# 6_H-bridge2.net
KiCad netlist of a schematic drawn in Altium Designer
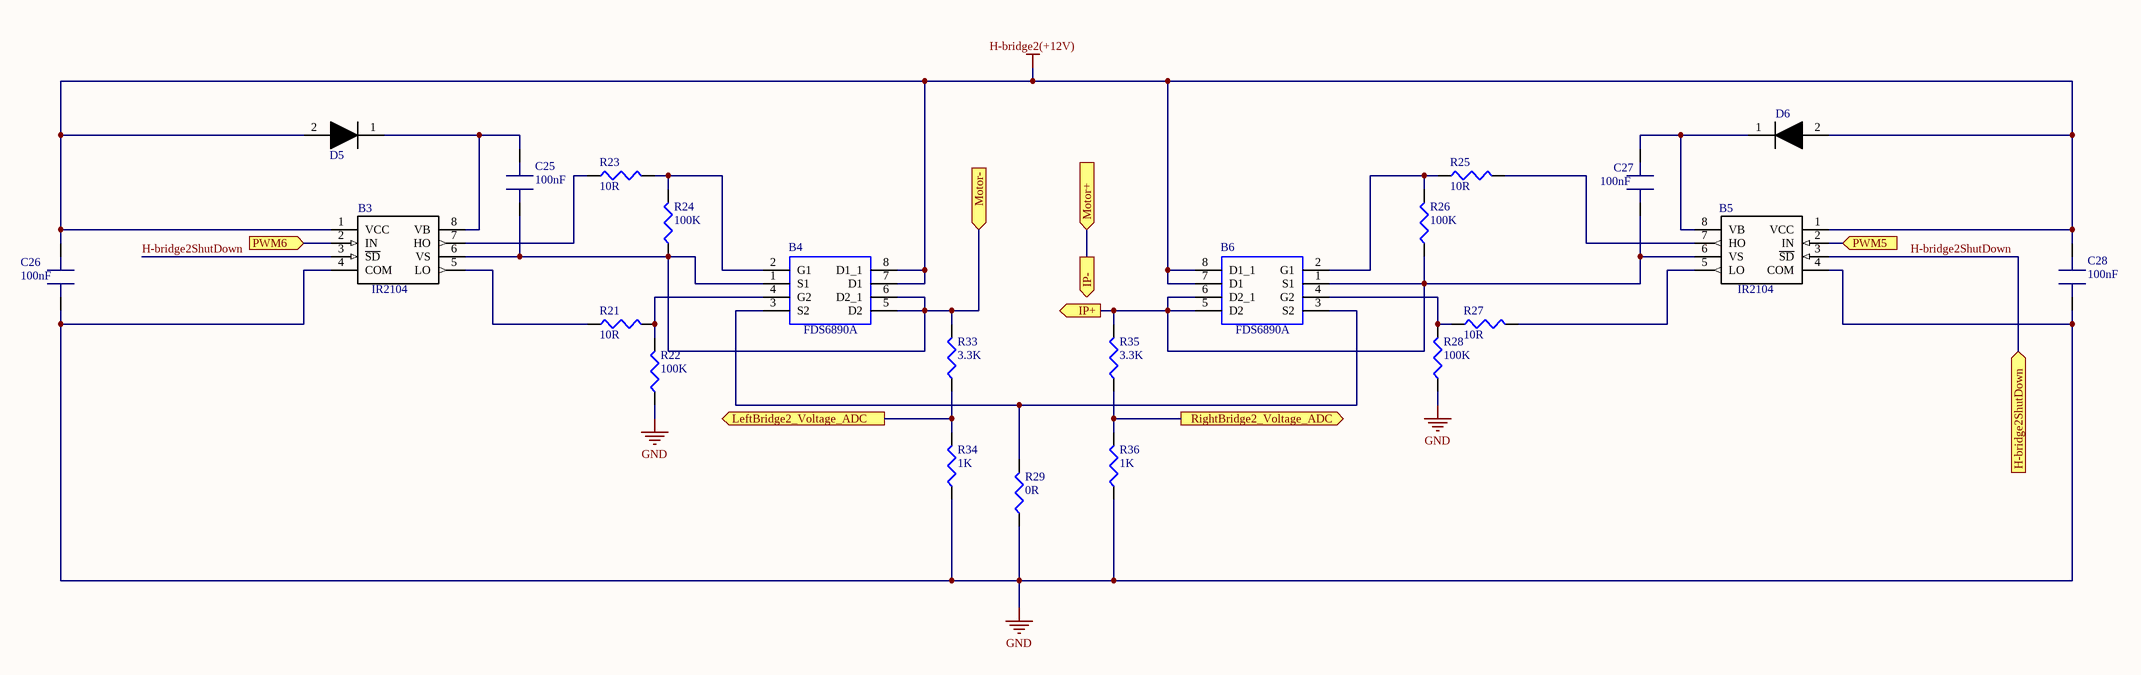
[diagram p0: [6]H-bridge2.SchDoc]

(export (version "E")
  (design (tool "Eeschema 10.0.6"))
  (components
    (comp (ref "B3")
      (value "IR2104")
      (footprint "*SOIC127P600X175-8N")
      (fields
        (field (name "MP") "IR2104STRPBF")
        (field (name "DIGI-KEY_PART_NUMBER") "IR2104SPBFCT-ND")
        (field (name "MF") "Infineon Technologies")
      )
      (libsource (lib "IR2104STRPBF") (part "IR2104STRPBF"))
    )
    (comp (ref "B4")
      (value "FDS6890A")
      (footprint "SOIC127P600X175-8N")
      (description "FDS6890A, Dual N-channel MOSFET Transistor 7.5 A 20 V, 8-Pin SOIC")
      (fields (field (name "RS PART NUMBER") "6710633P") (field (name "MOUSER PART NUMBER") "512-FDS6890A"))
      (libsource (lib "FDS6890A") (part "FDS6890A"))
    )
    (comp (ref "B5")
      (value "IR2104")
      (footprint "*SOIC127P600X175-8N")
      (fields
        (field (name "MP") "IR2104STRPBF")
        (field (name "DIGI-KEY_PART_NUMBER") "IR2104SPBFCT-ND")
        (field (name "MF") "Infineon Technologies")
      )
      (libsource (lib "IR2104STRPBF") (part "IR2104STRPBF"))
    )
    (comp (ref "B6")
      (value "FDS6890A")
      (footprint "SOIC127P600X175-8N")
      (description "FDS6890A, Dual N-channel MOSFET Transistor 7.5 A 20 V, 8-Pin SOIC")
      (fields (field (name "RS PART NUMBER") "6710633P") (field (name "MOUSER PART NUMBER") "512-FDS6890A"))
      (libsource (lib "FDS6890A") (part "FDS6890A"))
    )
    (comp (ref "C25") (value "100nF") (footprint "cap_805") (libsource (lib "Driver") (part "cap805")))
    (comp (ref "C26") (value "100nF") (footprint "cap_805") (libsource (lib "Driver") (part "cap805")))
    (comp (ref "C27") (value "100nF") (footprint "cap_805") (libsource (lib "Driver") (part "cap805")))
    (comp (ref "C28") (value "100nF") (footprint "cap_805") (libsource (lib "Driver") (part "cap805")))
    (comp (ref "D5") (value "Doide_SS34") (footprint "Doide_SS34") (libsource (lib "CM") (part "Doide_SS34")))
    (comp (ref "D6") (value "Doide_SS34") (footprint "Doide_SS34") (libsource (lib "CM") (part "Doide_SS34")))
    (comp (ref "R21") (value "10R") (footprint "Res805") (libsource (lib "Driver") (part "Res805")))
    (comp (ref "R22") (value "100K") (footprint "Res805") (libsource (lib "Driver") (part "Res805")))
    (comp (ref "R23") (value "10R") (footprint "Res805") (libsource (lib "Driver") (part "Res805")))
    (comp (ref "R24") (value "100K") (footprint "Res805") (libsource (lib "Driver") (part "Res805")))
    (comp (ref "R25") (value "10R") (footprint "Res805") (libsource (lib "Driver") (part "Res805")))
    (comp (ref "R26") (value "100K") (footprint "Res805") (libsource (lib "Driver") (part "Res805")))
    (comp (ref "R27") (value "10R") (footprint "Res805") (libsource (lib "Driver") (part "Res805")))
    (comp (ref "R28") (value "100K") (footprint "Res805") (libsource (lib "Driver") (part "Res805")))
    (comp (ref "R29") (value "0R") (footprint "Res805") (libsource (lib "Driver") (part "Res805")))
    (comp (ref "R33") (value "3.3K") (footprint "Res805") (libsource (lib "Driver") (part "Res805")))
    (comp (ref "R34") (value "1K") (footprint "Res805") (libsource (lib "Driver") (part "Res805")))
    (comp (ref "R35") (value "3.3K") (footprint "Res805") (libsource (lib "Driver") (part "Res805")))
    (comp (ref "R36") (value "1K") (footprint "Res805") (libsource (lib "Driver") (part "Res805")))
  )
  (nets
    (net (code "1") (name "/H-bridge2ShutDown") (class "Default")
      (node (ref "B3") (pin "3") (pinfunction "~{SD}_3") (pintype "input"))
      (node (ref "B5") (pin "3") (pinfunction "~{SD}_3") (pintype "input"))
    )
    (net (code "2") (name "/IP+") (class "Default")
      (node (ref "B5") (pin "6") (pinfunction "VS_6") (pintype "power_in"))
      (node (ref "B6") (pin "1") (pinfunction "S1_1") (pintype "passive"))
      (node (ref "B6") (pin "5") (pinfunction "D2_5") (pintype "passive"))
      (node (ref "B6") (pin "6") (pinfunction "D2_1_6") (pintype "passive"))
      (node (ref "C27") (pin "1") (pinfunction "1_1") (pintype "passive"))
      (node (ref "R26") (pin "1") (pinfunction "1_1") (pintype "passive"))
      (node (ref "R35") (pin "2") (pinfunction "2_2") (pintype "passive"))
    )
    (net (code "4") (name "/LeftBridge2_Voltage_ADC") (class "Default")
      (node (ref "R33") (pin "1") (pinfunction "1_1") (pintype "passive"))
      (node (ref "R34") (pin "2") (pinfunction "2_2") (pintype "passive"))
    )
    (net (code "5") (name "/Motor-") (class "Default")
      (node (ref "B3") (pin "6") (pinfunction "VS_6") (pintype "power_in"))
      (node (ref "B4") (pin "1") (pinfunction "S1_1") (pintype "passive"))
      (node (ref "B4") (pin "5") (pinfunction "D2_5") (pintype "passive"))
      (node (ref "B4") (pin "6") (pinfunction "D2_1_6") (pintype "passive"))
      (node (ref "C25") (pin "1") (pinfunction "1_1") (pintype "passive"))
      (node (ref "R24") (pin "1") (pinfunction "1_1") (pintype "passive"))
      (node (ref "R33") (pin "2") (pinfunction "2_2") (pintype "passive"))
    )
    (net (code "6") (name "/PWM5") (class "Default")
      (node (ref "B5") (pin "2") (pinfunction "IN_2") (pintype "input"))
    )
    (net (code "7") (name "/PWM6") (class "Default")
      (node (ref "B3") (pin "2") (pinfunction "IN_2") (pintype "input"))
    )
    (net (code "8") (name "/RightBridge2_Voltage_ADC") (class "Default")
      (node (ref "R35") (pin "1") (pinfunction "1_1") (pintype "passive"))
      (node (ref "R36") (pin "2") (pinfunction "2_2") (pintype "passive"))
    )
    (net (code "9") (name "GND") (class "Default")
      (node (ref "B3") (pin "4") (pinfunction "COM_4") (pintype "passive"))
      (node (ref "B5") (pin "4") (pinfunction "COM_4") (pintype "passive"))
      (node (ref "C26") (pin "1") (pinfunction "1_1") (pintype "passive"))
      (node (ref "C28") (pin "1") (pinfunction "1_1") (pintype "passive"))
      (node (ref "R22") (pin "1") (pinfunction "1_1") (pintype "passive"))
      (node (ref "R28") (pin "1") (pinfunction "1_1") (pintype "passive"))
      (node (ref "R29") (pin "1") (pinfunction "1_1") (pintype "passive"))
      (node (ref "R34") (pin "1") (pinfunction "1_1") (pintype "passive"))
      (node (ref "R36") (pin "1") (pinfunction "1_1") (pintype "passive"))
    )
    (net (code "10") (name "H-bridge2(+12V)") (class "Default")
      (node (ref "B3") (pin "1") (pinfunction "VCC_1") (pintype "power_in"))
      (node (ref "B4") (pin "7") (pinfunction "D1_7") (pintype "passive"))
      (node (ref "B4") (pin "8") (pinfunction "D1_1_8") (pintype "passive"))
      (node (ref "B5") (pin "1") (pinfunction "VCC_1") (pintype "power_in"))
      (node (ref "B6") (pin "7") (pinfunction "D1_7") (pintype "passive"))
      (node (ref "B6") (pin "8") (pinfunction "D1_1_8") (pintype "passive"))
      (node (ref "C26") (pin "2") (pinfunction "2_2") (pintype "passive"))
      (node (ref "C28") (pin "2") (pinfunction "2_2") (pintype "passive"))
      (node (ref "D5") (pin "2") (pinfunction "2_2") (pintype "passive"))
      (node (ref "D6") (pin "2") (pinfunction "2_2") (pintype "passive"))
    )
    (net (code "11") (name "Net-(B3-HO)") (class "Default")
      (node (ref "B3") (pin "7") (pinfunction "HO_7") (pintype "output"))
      (node (ref "R23") (pin "1") (pinfunction "1_1") (pintype "passive"))
    )
    (net (code "12") (name "Net-(B3-LO)") (class "Default")
      (node (ref "B3") (pin "5") (pinfunction "LO_5") (pintype "output"))
      (node (ref "R21") (pin "1") (pinfunction "1_1") (pintype "passive"))
    )
    (net (code "13") (name "Net-(B3-VB)") (class "Default")
      (node (ref "B3") (pin "8") (pinfunction "VB_8") (pintype "power_in"))
      (node (ref "C25") (pin "2") (pinfunction "2_2") (pintype "passive"))
      (node (ref "D5") (pin "1") (pinfunction "1_1") (pintype "passive"))
    )
    (net (code "14") (name "Net-(B4-G1)") (class "Default")
      (node (ref "B4") (pin "2") (pinfunction "G1_2") (pintype "passive"))
      (node (ref "R23") (pin "2") (pinfunction "2_2") (pintype "passive"))
      (node (ref "R24") (pin "2") (pinfunction "2_2") (pintype "passive"))
    )
    (net (code "15") (name "Net-(B4-G2)") (class "Default")
      (node (ref "B4") (pin "4") (pinfunction "G2_4") (pintype "passive"))
      (node (ref "R21") (pin "2") (pinfunction "2_2") (pintype "passive"))
      (node (ref "R22") (pin "2") (pinfunction "2_2") (pintype "passive"))
    )
    (net (code "16") (name "Net-(B4-S2)") (class "Default")
      (node (ref "B4") (pin "3") (pinfunction "S2_3") (pintype "passive"))
      (node (ref "B6") (pin "3") (pinfunction "S2_3") (pintype "passive"))
      (node (ref "R29") (pin "2") (pinfunction "2_2") (pintype "passive"))
    )
    (net (code "17") (name "Net-(B5-HO)") (class "Default")
      (node (ref "B5") (pin "7") (pinfunction "HO_7") (pintype "output"))
      (node (ref "R25") (pin "2") (pinfunction "2_2") (pintype "passive"))
    )
    (net (code "18") (name "Net-(B5-LO)") (class "Default")
      (node (ref "B5") (pin "5") (pinfunction "LO_5") (pintype "output"))
      (node (ref "R27") (pin "2") (pinfunction "2_2") (pintype "passive"))
    )
    (net (code "19") (name "Net-(B5-VB)") (class "Default")
      (node (ref "B5") (pin "8") (pinfunction "VB_8") (pintype "power_in"))
      (node (ref "C27") (pin "2") (pinfunction "2_2") (pintype "passive"))
      (node (ref "D6") (pin "1") (pinfunction "1_1") (pintype "passive"))
    )
    (net (code "20") (name "Net-(B6-G1)") (class "Default")
      (node (ref "B6") (pin "2") (pinfunction "G1_2") (pintype "passive"))
      (node (ref "R25") (pin "1") (pinfunction "1_1") (pintype "passive"))
      (node (ref "R26") (pin "2") (pinfunction "2_2") (pintype "passive"))
    )
    (net (code "21") (name "Net-(B6-G2)") (class "Default")
      (node (ref "B6") (pin "4") (pinfunction "G2_4") (pintype "passive"))
      (node (ref "R27") (pin "1") (pinfunction "1_1") (pintype "passive"))
      (node (ref "R28") (pin "2") (pinfunction "2_2") (pintype "passive"))
    )
  )
)
